# M5_STACK_STAMP_C3_ISOBUS_DTF.net
KiCad netlist of a schematic drawn in EAGLE
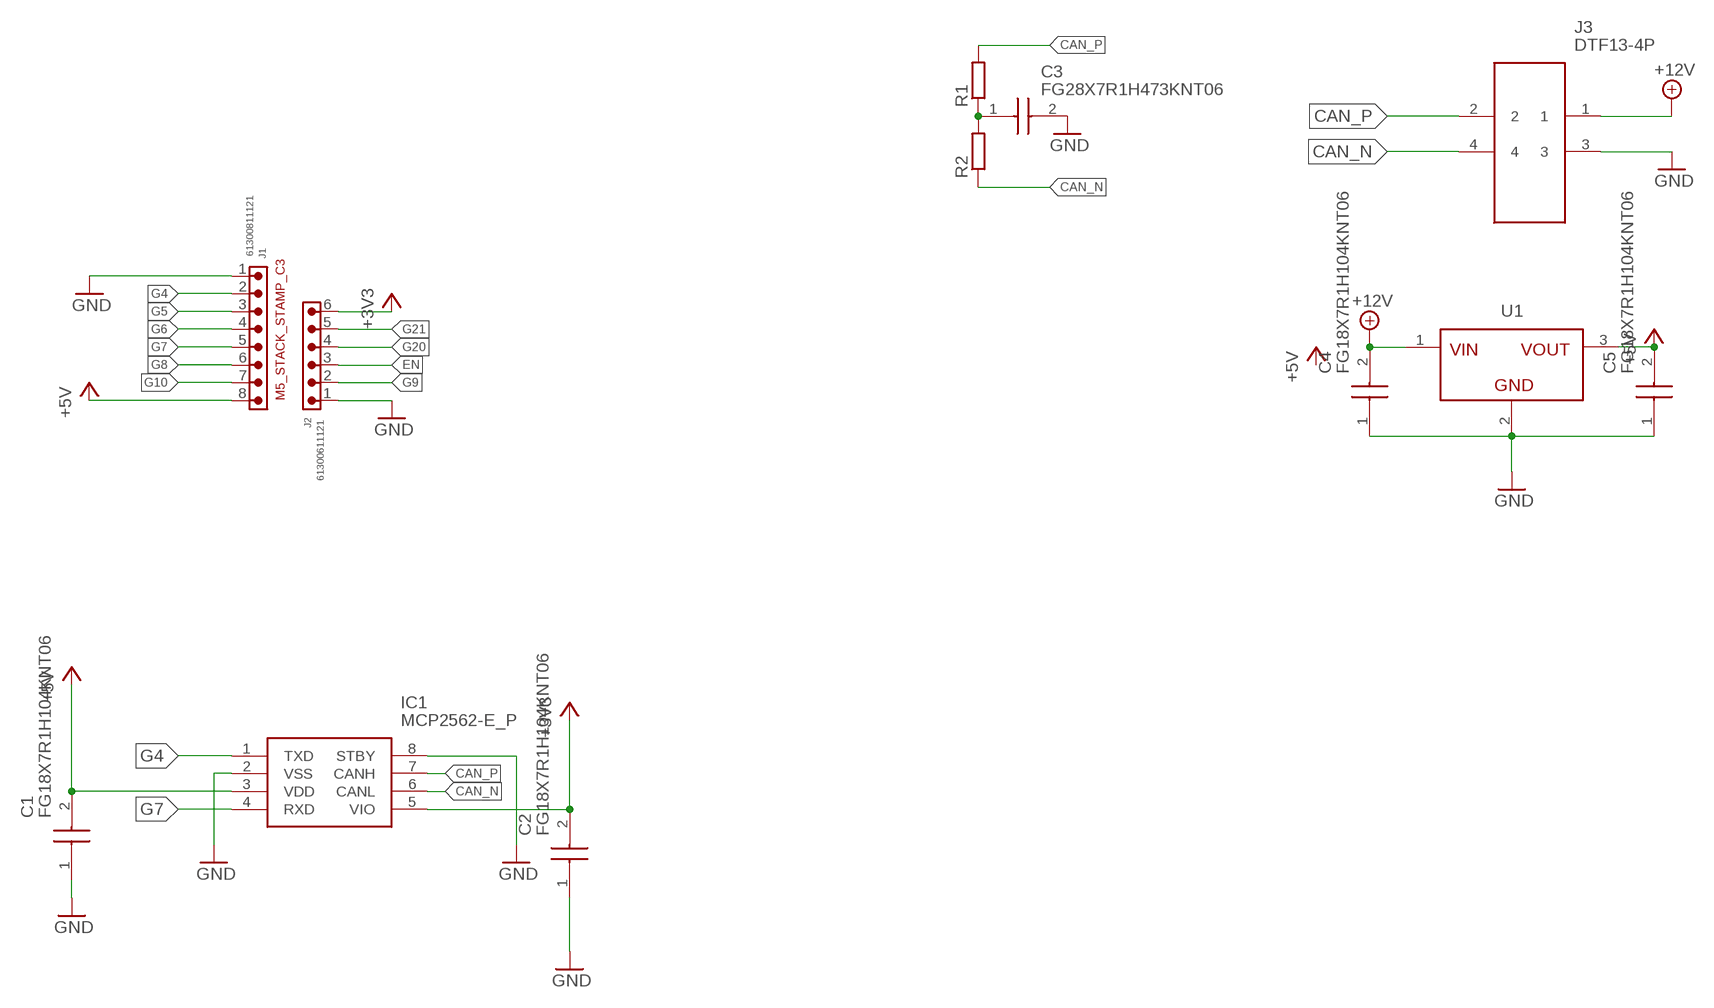
[diagram p0: schematic, sheet 1]

(export (version "E")
  (design (tool "Eeschema 10.0.6"))
  (components
    (comp (ref "C1")
      (value "FG18X7R1H104KNT06")
      (footprint "eagle-import:FG18C0G1H101JNT06")
      (fields (field (name "MOUSER_PART_NUMBER") "810-FG18X7R1H104KNT6"))
      (libsource (lib "eagle-import") (part "FG18X7R1H104KNT06"))
    )
    (comp (ref "C2")
      (value "FG18X7R1H104KNT06")
      (footprint "eagle-import:FG18C0G1H101JNT06")
      (fields (field (name "MOUSER_PART_NUMBER") "810-FG18X7R1H104KNT6"))
      (libsource (lib "eagle-import") (part "FG18X7R1H104KNT06"))
    )
    (comp (ref "C3")
      (value "FG28X7R1H473KNT06")
      (footprint "eagle-import:FG28")
      (fields (field (name "MOUSER_PART_NUMBER") "810-FG28X7R1H473KNT6"))
      (libsource (lib "eagle-import") (part "FG28X7R1H473KNT06"))
    )
    (comp (ref "C4")
      (value "FG18X7R1H104KNT06")
      (footprint "eagle-import:FG18C0G1H101JNT06")
      (fields (field (name "MOUSER_PART_NUMBER") "810-FG18X7R1H104KNT6"))
      (libsource (lib "eagle-import") (part "FG18X7R1H104KNT06"))
    )
    (comp (ref "C5")
      (value "FG18X7R1H104KNT06")
      (footprint "eagle-import:FG18C0G1H101JNT06")
      (fields (field (name "MOUSER_PART_NUMBER") "810-FG18X7R1H104KNT6"))
      (libsource (lib "eagle-import") (part "FG18X7R1H104KNT06"))
    )
    (comp (ref "IC1")
      (value "MCP2562-E_P")
      (footprint "eagle-import:DIP781W56P254L950H533Q8N")
      (fields
        (field (name "MANUFACTURER_PART_NUMBER") "MCP2562-E/P")
        (field (name "MOUSER_PART_NUMBER") "579-MCP2562-E/P")
      )
      (libsource (lib "eagle-import") (part "MCP2562-E_P"))
    )
    (comp (ref "J1")
      (value "61300811121")
      (footprint "eagle-import:61300811121")
      (libsource (lib "eagle-import") (part "6130XX11121_61300811121"))
    )
    (comp (ref "J2")
      (value "61300611121")
      (footprint "eagle-import:61300611121")
      (libsource (lib "eagle-import") (part "6130XX11121_61300611121"))
    )
    (comp (ref "J3")
      (value "DTF13-4P")
      (footprint "eagle-import:DTF134P")
      (fields (field (name "MOUSER_PART_NUMBER") "571-DTF13-4P"))
      (libsource (lib "eagle-import") (part "DTF13-4P"))
    )
    (comp (ref "R1")
      (value "R-EU_0204/7")
      (footprint "eagle-import:0204_7")
      (libsource (lib "eagle-import") (part "R-EU_0204/7"))
    )
    (comp (ref "R2")
      (value "R-EU_0204/7")
      (footprint "eagle-import:0204_7")
      (libsource (lib "eagle-import") (part "R-EU_0204/7"))
    )
    (comp (ref "U$1")
      (value "M5_STACK_STAMP_C3")
      (footprint "eagle-import:M5_STACK_STAMP_C3")
      (libsource (lib "eagle-import") (part "M5_STACK_STAMP_C3"))
    )
    (comp (ref "U1")
      (value "MAGI³C-FDSM_SIP-3_173010542_173XXXX42")
      (footprint "eagle-import:MAGI³C-FDSM_173XXXX42")
      (libsource (lib "eagle-import") (part "MAGI³C-FDSM_SIP-3_173XXXX42_173010542"))
    )
  )
  (nets
    (net (code "1") (name "+3V3") (class "Default")
      (node (ref "C2") (pin "2") (pinfunction "2_2") (pintype "bidirectional"))
      (node (ref "IC1") (pin "5") (pinfunction "VIO_5") (pintype "bidirectional"))
      (node (ref "J2") (pin "6") (pinfunction "6_6") (pintype "passive"))
    )
    (net (code "2") (name "+5V") (class "Default")
      (node (ref "C1") (pin "2") (pinfunction "2_2") (pintype "bidirectional"))
      (node (ref "C5") (pin "2") (pinfunction "2_2") (pintype "bidirectional"))
      (node (ref "IC1") (pin "3") (pinfunction "VDD_3") (pintype "bidirectional"))
      (node (ref "J1") (pin "8") (pinfunction "8_8") (pintype "passive"))
      (node (ref "U1") (pin "3") (pinfunction "VOUT_3") (pintype "output"))
    )
    (net (code "3") (name "+12V") (class "Default")
      (node (ref "C4") (pin "2") (pinfunction "2_2") (pintype "bidirectional"))
      (node (ref "J3") (pin "1") (pinfunction "1_1") (pintype "bidirectional"))
      (node (ref "U1") (pin "1") (pinfunction "VIN_1") (pintype "input"))
    )
    (net (code "4") (name "CAN_N") (class "Default")
      (node (ref "IC1") (pin "6") (pinfunction "CANL_6") (pintype "bidirectional"))
      (node (ref "J3") (pin "4") (pinfunction "4_4") (pintype "bidirectional"))
      (node (ref "R2") (pin "1") (pinfunction "1_1") (pintype "passive"))
    )
    (net (code "5") (name "CAN_P") (class "Default")
      (node (ref "IC1") (pin "7") (pinfunction "CANH_7") (pintype "bidirectional"))
      (node (ref "J3") (pin "2") (pinfunction "2_2") (pintype "bidirectional"))
      (node (ref "R1") (pin "2") (pinfunction "2_2") (pintype "passive"))
    )
    (net (code "6") (name "EN") (class "Default")
      (node (ref "J2") (pin "3") (pinfunction "3_3") (pintype "passive"))
    )
    (net (code "7") (name "G4") (class "Default")
      (node (ref "IC1") (pin "1") (pinfunction "TXD_1") (pintype "bidirectional"))
      (node (ref "J1") (pin "2") (pinfunction "2_2") (pintype "passive"))
    )
    (net (code "8") (name "G5") (class "Default")
      (node (ref "J1") (pin "3") (pinfunction "3_3") (pintype "passive"))
    )
    (net (code "9") (name "G6") (class "Default")
      (node (ref "J1") (pin "4") (pinfunction "4_4") (pintype "passive"))
    )
    (net (code "10") (name "G7") (class "Default")
      (node (ref "IC1") (pin "4") (pinfunction "RXD_4") (pintype "bidirectional"))
      (node (ref "J1") (pin "5") (pinfunction "5_5") (pintype "passive"))
    )
    (net (code "11") (name "G8") (class "Default")
      (node (ref "J1") (pin "6") (pinfunction "6_6") (pintype "passive"))
    )
    (net (code "12") (name "G9") (class "Default")
      (node (ref "J2") (pin "2") (pinfunction "2_2") (pintype "passive"))
    )
    (net (code "13") (name "G10") (class "Default")
      (node (ref "J1") (pin "7") (pinfunction "7_7") (pintype "passive"))
    )
    (net (code "14") (name "G20") (class "Default")
      (node (ref "J2") (pin "4") (pinfunction "4_4") (pintype "passive"))
    )
    (net (code "15") (name "G21") (class "Default")
      (node (ref "J2") (pin "5") (pinfunction "5_5") (pintype "passive"))
    )
    (net (code "16") (name "GND") (class "Default")
      (node (ref "C1") (pin "1") (pinfunction "1_1") (pintype "bidirectional"))
      (node (ref "C2") (pin "1") (pinfunction "1_1") (pintype "bidirectional"))
      (node (ref "C3") (pin "2") (pinfunction "2_2") (pintype "bidirectional"))
      (node (ref "C4") (pin "1") (pinfunction "1_1") (pintype "bidirectional"))
      (node (ref "C5") (pin "1") (pinfunction "1_1") (pintype "bidirectional"))
      (node (ref "IC1") (pin "2") (pinfunction "VSS_2") (pintype "bidirectional"))
      (node (ref "IC1") (pin "8") (pinfunction "STBY_8") (pintype "bidirectional"))
      (node (ref "J1") (pin "1") (pinfunction "1_1") (pintype "passive"))
      (node (ref "J2") (pin "1") (pinfunction "1_1") (pintype "passive"))
      (node (ref "J3") (pin "3") (pinfunction "3_3") (pintype "bidirectional"))
      (node (ref "U1") (pin "2") (pinfunction "GND_2") (pintype "passive"))
    )
    (net (code "17") (name "Net-(C3-Pad1)") (class "Default")
      (node (ref "C3") (pin "1") (pinfunction "1_1") (pintype "bidirectional"))
      (node (ref "R1") (pin "1") (pinfunction "1_1") (pintype "passive"))
      (node (ref "R2") (pin "2") (pinfunction "2_2") (pintype "passive"))
    )
  )
)
